# motherboard.net
KiCad netlist of a schematic drawn in EAGLE
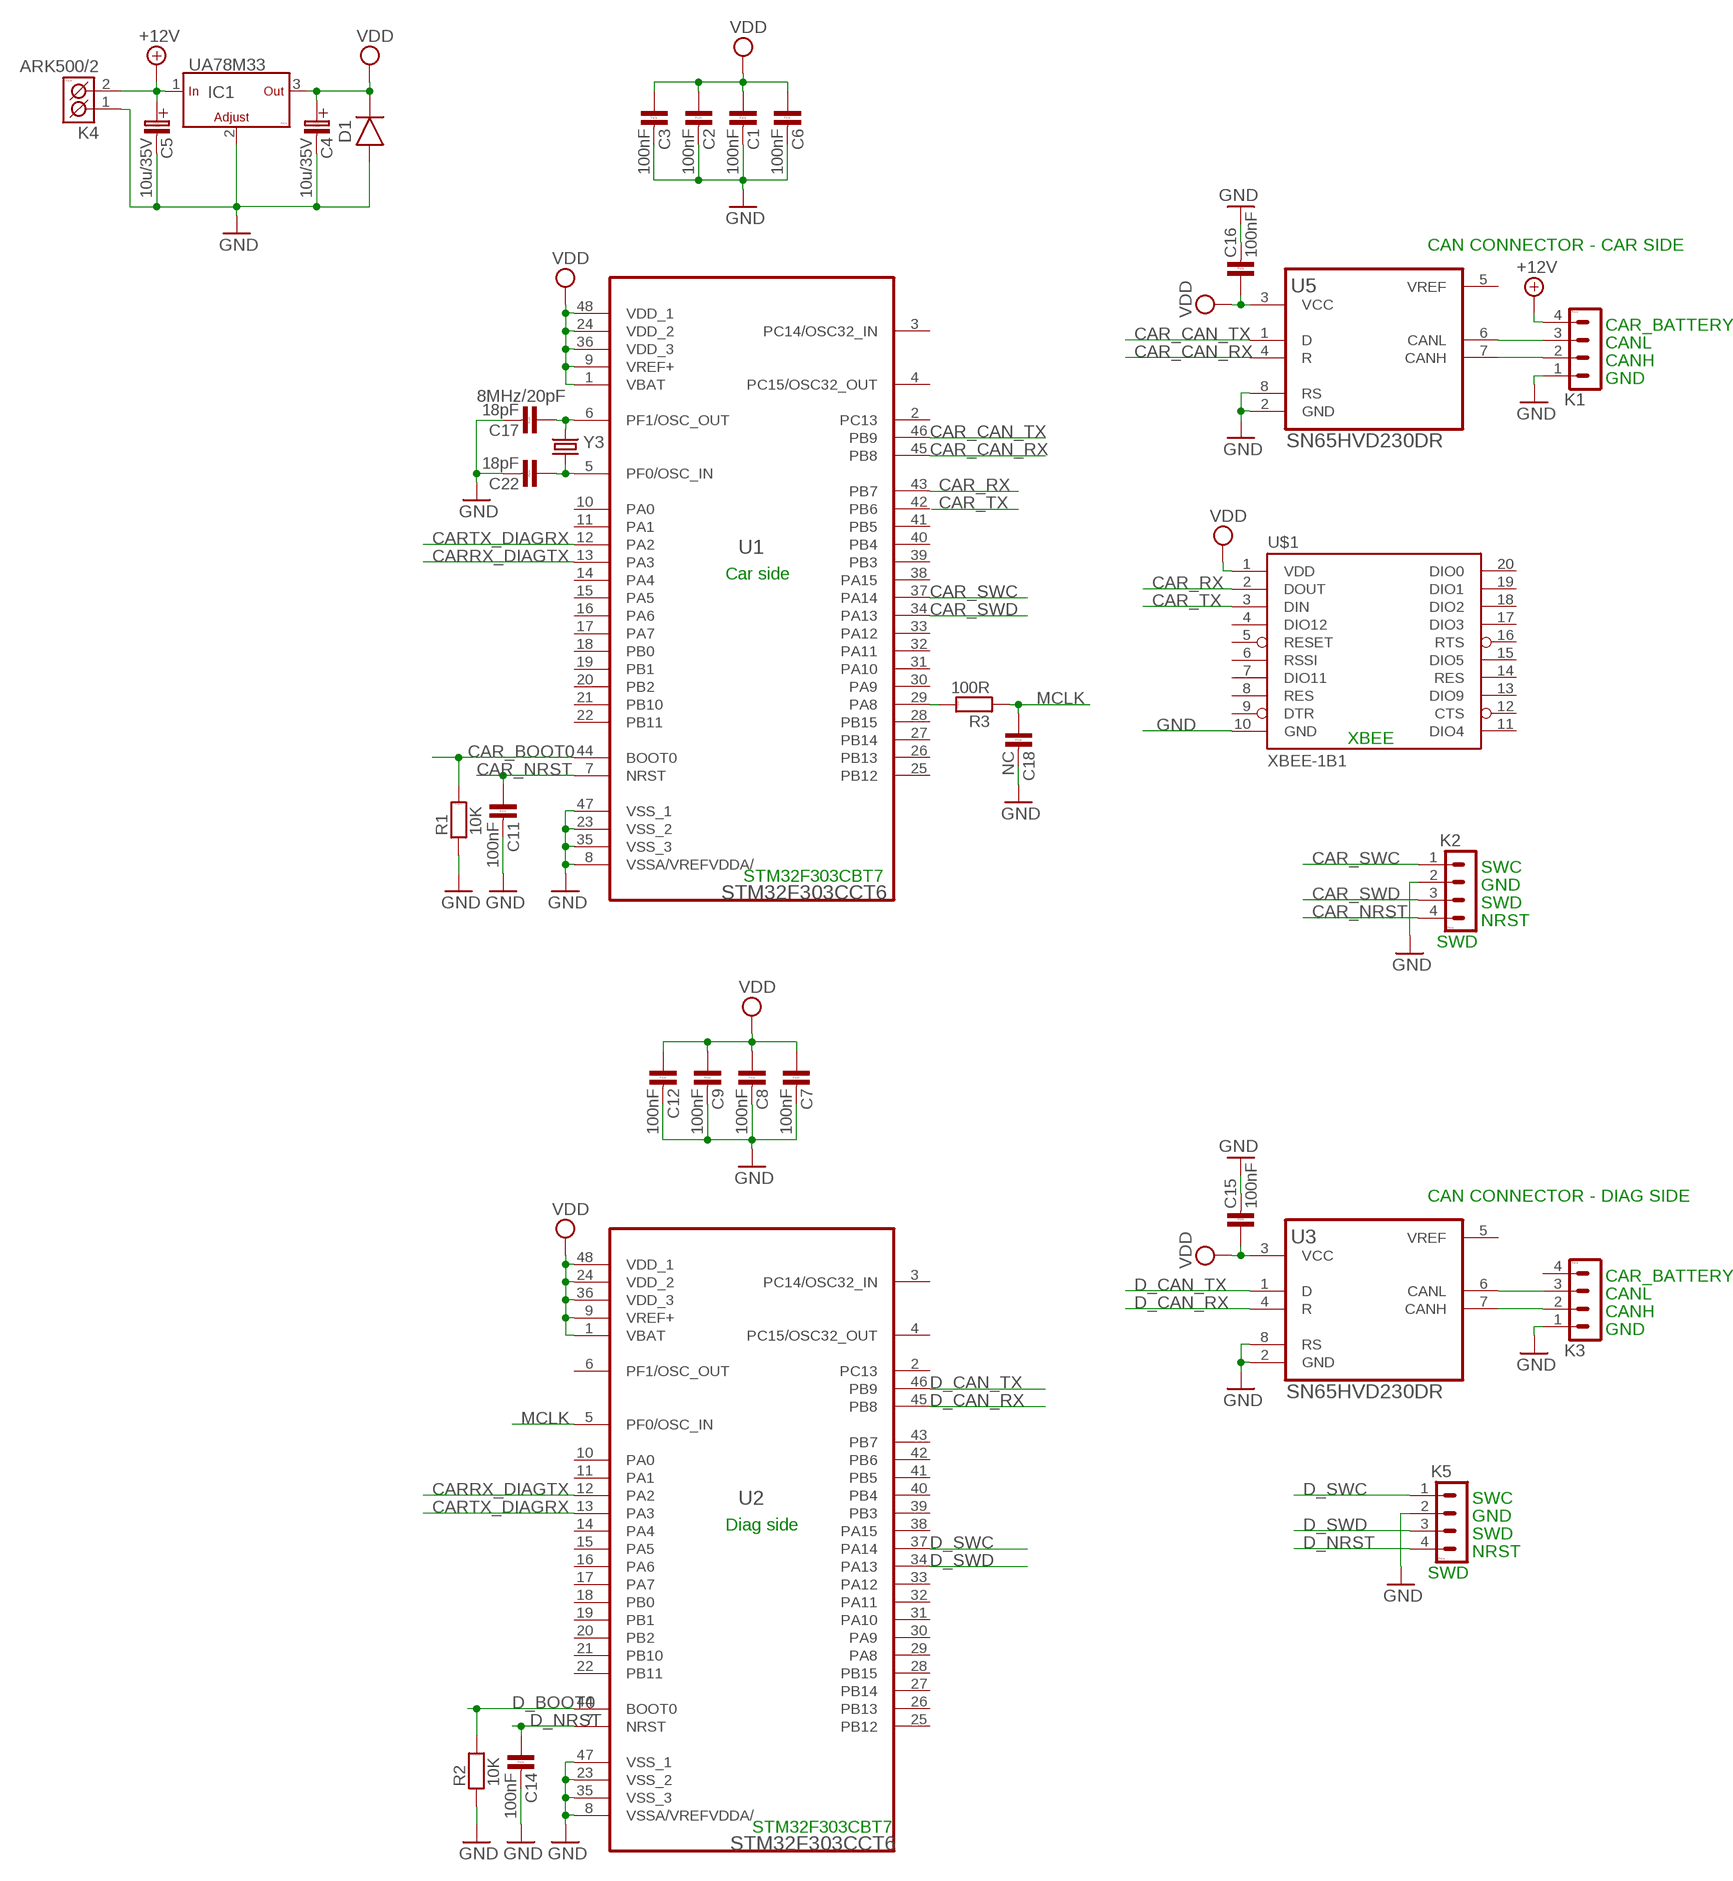
[diagram p0: schematic, sheet 1]

(export (version "E")
  (design (tool "Eeschema 10.0.6"))
  (components
    (comp (ref "C1")
      (value "100nF")
      (footprint "eagle-import:0805")
      (libsource (lib "eagle-import") (part "C-KERAMIK_SMD_0805"))
    )
    (comp (ref "C2")
      (value "100nF")
      (footprint "eagle-import:0805")
      (libsource (lib "eagle-import") (part "C-KERAMIK_SMD_0805"))
    )
    (comp (ref "C3")
      (value "100nF")
      (footprint "eagle-import:0805")
      (libsource (lib "eagle-import") (part "C-KERAMIK_SMD_0805"))
    )
    (comp (ref "C4")
      (value "10u/35V")
      (footprint "eagle-import:C-EL_2,5")
      (libsource (lib "eagle-import") (part "C-ELEKTROLYT_2,5"))
    )
    (comp (ref "C5")
      (value "10u/35V")
      (footprint "eagle-import:C-EL_2,5")
      (libsource (lib "eagle-import") (part "C-ELEKTROLYT_2,5"))
    )
    (comp (ref "C6")
      (value "100nF")
      (footprint "eagle-import:0805")
      (libsource (lib "eagle-import") (part "C-KERAMIK_SMD_0805"))
    )
    (comp (ref "C7")
      (value "100nF")
      (footprint "eagle-import:0805")
      (libsource (lib "eagle-import") (part "C-KERAMIK_SMD_0805"))
    )
    (comp (ref "C8")
      (value "100nF")
      (footprint "eagle-import:0805")
      (libsource (lib "eagle-import") (part "C-KERAMIK_SMD_0805"))
    )
    (comp (ref "C9")
      (value "100nF")
      (footprint "eagle-import:0805")
      (libsource (lib "eagle-import") (part "C-KERAMIK_SMD_0805"))
    )
    (comp (ref "C11")
      (value "100nF")
      (footprint "eagle-import:0805")
      (libsource (lib "eagle-import") (part "C-KERAMIK_SMD_0805"))
    )
    (comp (ref "C12")
      (value "100nF")
      (footprint "eagle-import:0805")
      (libsource (lib "eagle-import") (part "C-KERAMIK_SMD_0805"))
    )
    (comp (ref "C14")
      (value "100nF")
      (footprint "eagle-import:0805")
      (libsource (lib "eagle-import") (part "C-KERAMIK_SMD_0805"))
    )
    (comp (ref "C15")
      (value "100nF")
      (footprint "eagle-import:0805")
      (libsource (lib "eagle-import") (part "C-KERAMIK_SMD_0805"))
    )
    (comp (ref "C16")
      (value "100nF")
      (footprint "eagle-import:0805")
      (libsource (lib "eagle-import") (part "C-KERAMIK_SMD_0805"))
    )
    (comp (ref "C17")
      (value "18pF")
      (footprint "eagle-import:1206")
      (libsource (lib "eagle-import") (part "C-KERAMIK_SMD_1206"))
    )
    (comp (ref "C18")
      (value "NC")
      (footprint "eagle-import:0805")
      (libsource (lib "eagle-import") (part "C-KERAMIK_SMD_0805"))
    )
    (comp (ref "C22")
      (value "18pF")
      (footprint "eagle-import:1206")
      (libsource (lib "eagle-import") (part "C-KERAMIK_SMD_1206"))
    )
    (comp (ref "D1")
      (value "1N4007SMD")
      (footprint "eagle-import:MELF")
      (libsource (lib "eagle-import") (part "1N4007SMD"))
    )
    (comp (ref "IC1")
      (value "UA78M33")
      (footprint "eagle-import:TO285P991X230-3N")
      (fields (field (name "MPN") "UA78M33CKVURG3"))
      (libsource (lib "eagle-import") (part "UA78M33"))
    )
    (comp (ref "K1")
      (value "PSH02-04P")
      (footprint "eagle-import:PSH02-04P")
      (libsource (lib "eagle-import") (part "PSH02-04P"))
    )
    (comp (ref "K2")
      (value "PSH02-04P")
      (footprint "eagle-import:PSH02-04P")
      (libsource (lib "eagle-import") (part "PSH02-04P"))
    )
    (comp (ref "K3")
      (value "PSH02-04P")
      (footprint "eagle-import:PSH02-04P")
      (libsource (lib "eagle-import") (part "PSH02-04P"))
    )
    (comp (ref "K4")
      (value "ARK500/2")
      (footprint "eagle-import:ARK500_2")
      (libsource (lib "eagle-import") (part "ARK500/2"))
    )
    (comp (ref "K5")
      (value "PSH02-04P")
      (footprint "eagle-import:PSH02-04P")
      (libsource (lib "eagle-import") (part "PSH02-04P"))
    )
    (comp (ref "R1")
      (value "10K")
      (footprint "eagle-import:0805")
      (libsource (lib "eagle-import") (part "R_SMD_0805"))
    )
    (comp (ref "R2")
      (value "10K")
      (footprint "eagle-import:0805")
      (libsource (lib "eagle-import") (part "R_SMD_0805"))
    )
    (comp (ref "R3")
      (value "100R")
      (footprint "eagle-import:0805")
      (libsource (lib "eagle-import") (part "R_SMD_0805"))
    )
    (comp (ref "U$1")
      (value "XBEE-1B1")
      (footprint "eagle-import:XBEE-1")
      (libsource (lib "eagle-import") (part "XBEE-1B1"))
    )
    (comp (ref "U1")
      (value "STM32F303CCT6")
      (footprint "eagle-import:QFP50P900X900X160-48N")
      (libsource (lib "eagle-import") (part "STM32F303CCT6"))
    )
    (comp (ref "U2")
      (value "STM32F303CCT6")
      (footprint "eagle-import:QFP50P900X900X160-48N")
      (libsource (lib "eagle-import") (part "STM32F303CCT6"))
    )
    (comp (ref "U3")
      (value "SN65HVD230DR")
      (footprint "eagle-import:SOIC127P600X175-8N")
      (libsource (lib "eagle-import") (part "SN65HVD230DR"))
    )
    (comp (ref "U5")
      (value "SN65HVD230DR")
      (footprint "eagle-import:SOIC127P600X175-8N")
      (libsource (lib "eagle-import") (part "SN65HVD230DR"))
    )
    (comp (ref "Y3")
      (value "8MHz/20pF")
      (footprint "eagle-import:HC49UP")
      (libsource (lib "eagle-import") (part "CRYSTALSMD"))
    )
  )
  (nets
    (net (code "1") (name "+12V") (class "Default")
      (node (ref "C5") (pin "C+") (pinfunction "C_EL+_C+") (pintype "passive"))
      (node (ref "IC1") (pin "1") (pinfunction "IN_1") (pintype "input"))
      (node (ref "K1") (pin "4") (pinfunction "4_4") (pintype "passive"))
      (node (ref "K4") (pin "2") (pinfunction "K2_2") (pintype "passive"))
    )
    (net (code "2") (name "/CARRX_DIAGTX") (class "Default")
      (node (ref "U1") (pin "13") (pinfunction "PA3_13") (pintype "bidirectional"))
      (node (ref "U2") (pin "12") (pinfunction "PA2_12") (pintype "bidirectional"))
    )
    (net (code "3") (name "/CARTX_DIAGRX") (class "Default")
      (node (ref "U1") (pin "12") (pinfunction "PA2_12") (pintype "bidirectional"))
      (node (ref "U2") (pin "13") (pinfunction "PA3_13") (pintype "bidirectional"))
    )
    (net (code "4") (name "/CAR_BOOT0") (class "Default")
      (node (ref "R1") (pin "2") (pinfunction "2_2") (pintype "passive"))
      (node (ref "U1") (pin "44") (pinfunction "BOOT0_44") (pintype "passive"))
    )
    (net (code "5") (name "/CAR_CAN_RX") (class "Default")
      (node (ref "U1") (pin "45") (pinfunction "PB8_45") (pintype "bidirectional"))
      (node (ref "U5") (pin "4") (pinfunction "R_4") (pintype "output"))
    )
    (net (code "6") (name "/CAR_CAN_TX") (class "Default")
      (node (ref "U1") (pin "46") (pinfunction "PB9_46") (pintype "bidirectional"))
      (node (ref "U5") (pin "1") (pinfunction "D_1") (pintype "input"))
    )
    (net (code "7") (name "/CAR_NRST") (class "Default")
      (node (ref "C11") (pin "1") (pinfunction "1_1") (pintype "passive"))
      (node (ref "K2") (pin "4") (pinfunction "4_4") (pintype "passive"))
      (node (ref "U1") (pin "7") (pinfunction "NRST_7") (pintype "passive"))
    )
    (net (code "8") (name "/CAR_RX") (class "Default")
      (node (ref "U$1") (pin "2") (pinfunction "DOUT_2") (pintype "output"))
      (node (ref "U1") (pin "43") (pinfunction "PB7_43") (pintype "bidirectional"))
    )
    (net (code "9") (name "/CAR_SWC") (class "Default")
      (node (ref "K2") (pin "1") (pinfunction "1_1") (pintype "passive"))
      (node (ref "U1") (pin "37") (pinfunction "PA14_37") (pintype "bidirectional"))
    )
    (net (code "10") (name "/CAR_SWD") (class "Default")
      (node (ref "K2") (pin "3") (pinfunction "3_3") (pintype "passive"))
      (node (ref "U1") (pin "34") (pinfunction "PA13_34") (pintype "bidirectional"))
    )
    (net (code "11") (name "/CAR_TX") (class "Default")
      (node (ref "U$1") (pin "3") (pinfunction "DIN_3") (pintype "input"))
    )
    (net (code "12") (name "/D_BOOT0") (class "Default")
      (node (ref "R2") (pin "2") (pinfunction "2_2") (pintype "passive"))
      (node (ref "U2") (pin "44") (pinfunction "BOOT0_44") (pintype "passive"))
    )
    (net (code "13") (name "/D_CAN_RX") (class "Default")
      (node (ref "U2") (pin "45") (pinfunction "PB8_45") (pintype "bidirectional"))
      (node (ref "U3") (pin "4") (pinfunction "R_4") (pintype "output"))
    )
    (net (code "14") (name "/D_CAN_TX") (class "Default")
      (node (ref "U2") (pin "46") (pinfunction "PB9_46") (pintype "bidirectional"))
      (node (ref "U3") (pin "1") (pinfunction "D_1") (pintype "input"))
    )
    (net (code "15") (name "/D_NRST") (class "Default")
      (node (ref "C14") (pin "1") (pinfunction "1_1") (pintype "passive"))
      (node (ref "K5") (pin "4") (pinfunction "4_4") (pintype "passive"))
      (node (ref "U2") (pin "7") (pinfunction "NRST_7") (pintype "passive"))
    )
    (net (code "16") (name "/D_SWC") (class "Default")
      (node (ref "K5") (pin "1") (pinfunction "1_1") (pintype "passive"))
      (node (ref "U2") (pin "37") (pinfunction "PA14_37") (pintype "bidirectional"))
    )
    (net (code "17") (name "/D_SWD") (class "Default")
      (node (ref "K5") (pin "3") (pinfunction "3_3") (pintype "passive"))
      (node (ref "U2") (pin "34") (pinfunction "PA13_34") (pintype "bidirectional"))
    )
    (net (code "18") (name "/MCLK") (class "Default")
      (node (ref "C18") (pin "1") (pinfunction "1_1") (pintype "passive"))
      (node (ref "R3") (pin "1") (pinfunction "1_1") (pintype "passive"))
      (node (ref "U2") (pin "5") (pinfunction "PF0/OSC_IN_5") (pintype "bidirectional"))
    )
    (net (code "19") (name "GND") (class "Default")
      (node (ref "C1") (pin "2") (pinfunction "2_2") (pintype "passive"))
      (node (ref "C11") (pin "2") (pinfunction "2_2") (pintype "passive"))
      (node (ref "C12") (pin "2") (pinfunction "2_2") (pintype "passive"))
      (node (ref "C14") (pin "2") (pinfunction "2_2") (pintype "passive"))
      (node (ref "C15") (pin "2") (pinfunction "2_2") (pintype "passive"))
      (node (ref "C16") (pin "2") (pinfunction "2_2") (pintype "passive"))
      (node (ref "C17") (pin "2") (pinfunction "2_2") (pintype "passive"))
      (node (ref "C18") (pin "2") (pinfunction "2_2") (pintype "passive"))
      (node (ref "C2") (pin "2") (pinfunction "2_2") (pintype "passive"))
      (node (ref "C22") (pin "2") (pinfunction "2_2") (pintype "passive"))
      (node (ref "C3") (pin "2") (pinfunction "2_2") (pintype "passive"))
      (node (ref "C4") (pin "C-") (pinfunction "C_EL-_C-") (pintype "passive"))
      (node (ref "C5") (pin "C-") (pinfunction "C_EL-_C-") (pintype "passive"))
      (node (ref "C6") (pin "2") (pinfunction "2_2") (pintype "passive"))
      (node (ref "C7") (pin "2") (pinfunction "2_2") (pintype "passive"))
      (node (ref "C8") (pin "2") (pinfunction "2_2") (pintype "passive"))
      (node (ref "C9") (pin "2") (pinfunction "2_2") (pintype "passive"))
      (node (ref "D1") (pin "A") (pinfunction "A_A") (pintype "passive"))
      (node (ref "IC1") (pin "2") (pinfunction "ADJ_2") (pintype "input"))
      (node (ref "K1") (pin "1") (pinfunction "1_1") (pintype "passive"))
      (node (ref "K2") (pin "2") (pinfunction "2_2") (pintype "passive"))
      (node (ref "K3") (pin "1") (pinfunction "1_1") (pintype "passive"))
      (node (ref "K4") (pin "1") (pinfunction "K1_1") (pintype "passive"))
      (node (ref "K5") (pin "2") (pinfunction "2_2") (pintype "passive"))
      (node (ref "R1") (pin "1") (pinfunction "1_1") (pintype "passive"))
      (node (ref "R2") (pin "1") (pinfunction "1_1") (pintype "passive"))
      (node (ref "U$1") (pin "10") (pinfunction "GND_10") (pintype "power_in"))
      (node (ref "U1") (pin "23") (pinfunction "VSS_2_23") (pintype "power_in"))
      (node (ref "U1") (pin "35") (pinfunction "VSS_3_35") (pintype "power_in"))
      (node (ref "U1") (pin "47") (pinfunction "VSS_1_47") (pintype "power_in"))
      (node (ref "U1") (pin "8") (pinfunction "VSSA/VREFVDDA/_8") (pintype "power_in"))
      (node (ref "U2") (pin "23") (pinfunction "VSS_2_23") (pintype "power_in"))
      (node (ref "U2") (pin "35") (pinfunction "VSS_3_35") (pintype "power_in"))
      (node (ref "U2") (pin "47") (pinfunction "VSS_1_47") (pintype "power_in"))
      (node (ref "U2") (pin "8") (pinfunction "VSSA/VREFVDDA/_8") (pintype "power_in"))
      (node (ref "U3") (pin "2") (pinfunction "GND_2") (pintype "passive"))
      (node (ref "U3") (pin "8") (pinfunction "RS_8") (pintype "input"))
      (node (ref "U5") (pin "2") (pinfunction "GND_2") (pintype "passive"))
      (node (ref "U5") (pin "8") (pinfunction "RS_8") (pintype "input"))
    )
    (net (code "20") (name "Net-(U1-PA8)") (class "Default")
      (node (ref "R3") (pin "2") (pinfunction "2_2") (pintype "passive"))
      (node (ref "U1") (pin "29") (pinfunction "PA8_29") (pintype "bidirectional"))
    )
    (net (code "21") (name "Net-(U1-PF0{slash}OSC_IN)") (class "Default")
      (node (ref "C22") (pin "1") (pinfunction "1_1") (pintype "passive"))
      (node (ref "U1") (pin "5") (pinfunction "PF0/OSC_IN_5") (pintype "bidirectional"))
      (node (ref "Y3") (pin "1") (pinfunction "1_1") (pintype "passive"))
    )
    (net (code "22") (name "Net-(U1-PF1{slash}OSC_OUT)") (class "Default")
      (node (ref "C17") (pin "1") (pinfunction "1_1") (pintype "passive"))
      (node (ref "U1") (pin "6") (pinfunction "PF1/OSC_OUT_6") (pintype "bidirectional"))
      (node (ref "Y3") (pin "2") (pinfunction "2_2") (pintype "passive"))
    )
    (net (code "23") (name "Net-(U3-CANH)") (class "Default")
      (node (ref "K3") (pin "2") (pinfunction "2_2") (pintype "passive"))
      (node (ref "U3") (pin "7") (pinfunction "CANH_7") (pintype "output"))
    )
    (net (code "24") (name "Net-(U3-CANL)") (class "Default")
      (node (ref "K3") (pin "3") (pinfunction "3_3") (pintype "passive"))
      (node (ref "U3") (pin "6") (pinfunction "CANL_6") (pintype "output"))
    )
    (net (code "25") (name "Net-(U5-CANH)") (class "Default")
      (node (ref "K1") (pin "2") (pinfunction "2_2") (pintype "passive"))
      (node (ref "U5") (pin "7") (pinfunction "CANH_7") (pintype "output"))
    )
    (net (code "26") (name "Net-(U5-CANL)") (class "Default")
      (node (ref "K1") (pin "3") (pinfunction "3_3") (pintype "passive"))
      (node (ref "U5") (pin "6") (pinfunction "CANL_6") (pintype "output"))
    )
    (net (code "27") (name "VDD") (class "Default")
      (node (ref "C1") (pin "1") (pinfunction "1_1") (pintype "passive"))
      (node (ref "C12") (pin "1") (pinfunction "1_1") (pintype "passive"))
      (node (ref "C15") (pin "1") (pinfunction "1_1") (pintype "passive"))
      (node (ref "C16") (pin "1") (pinfunction "1_1") (pintype "passive"))
      (node (ref "C2") (pin "1") (pinfunction "1_1") (pintype "passive"))
      (node (ref "C3") (pin "1") (pinfunction "1_1") (pintype "passive"))
      (node (ref "C4") (pin "C+") (pinfunction "C_EL+_C+") (pintype "passive"))
      (node (ref "C6") (pin "1") (pinfunction "1_1") (pintype "passive"))
      (node (ref "C7") (pin "1") (pinfunction "1_1") (pintype "passive"))
      (node (ref "C8") (pin "1") (pinfunction "1_1") (pintype "passive"))
      (node (ref "C9") (pin "1") (pinfunction "1_1") (pintype "passive"))
      (node (ref "D1") (pin "K") (pinfunction "K_K") (pintype "passive"))
      (node (ref "IC1") (pin "3") (pinfunction "OUT_3") (pintype "output"))
      (node (ref "U$1") (pin "1") (pinfunction "VDD_1") (pintype "power_in"))
      (node (ref "U1") (pin "1") (pinfunction "VBAT_1") (pintype "passive"))
      (node (ref "U1") (pin "24") (pinfunction "VDD_2_24") (pintype "power_in"))
      (node (ref "U1") (pin "36") (pinfunction "VDD_3_36") (pintype "power_in"))
      (node (ref "U1") (pin "48") (pinfunction "VDD_1_48") (pintype "power_in"))
      (node (ref "U1") (pin "9") (pinfunction "VREF+_9") (pintype "passive"))
      (node (ref "U2") (pin "1") (pinfunction "VBAT_1") (pintype "passive"))
      (node (ref "U2") (pin "24") (pinfunction "VDD_2_24") (pintype "power_in"))
      (node (ref "U2") (pin "36") (pinfunction "VDD_3_36") (pintype "power_in"))
      (node (ref "U2") (pin "48") (pinfunction "VDD_1_48") (pintype "power_in"))
      (node (ref "U2") (pin "9") (pinfunction "VREF+_9") (pintype "passive"))
      (node (ref "U3") (pin "3") (pinfunction "VCC_3") (pintype "power_in"))
      (node (ref "U5") (pin "3") (pinfunction "VCC_3") (pintype "power_in"))
    )
    (net (code "28") (name "unconnected-(K3-Pad4)") (class "Default")
      (node (ref "K3") (pin "4") (pinfunction "4_4") (pintype "passive"))
    )
    (net (code "29") (name "unconnected-(U$1-CTS-Pad12)") (class "Default")
      (node (ref "U$1") (pin "12") (pinfunction "CTS_12") (pintype "output"))
    )
    (net (code "30") (name "unconnected-(U$1-DIO0-Pad20)") (class "Default")
      (node (ref "U$1") (pin "20") (pinfunction "DIO0_20") (pintype "bidirectional"))
    )
    (net (code "31") (name "unconnected-(U$1-DIO1-Pad19)") (class "Default")
      (node (ref "U$1") (pin "19") (pinfunction "DIO1_19") (pintype "bidirectional"))
    )
    (net (code "32") (name "unconnected-(U$1-DIO2-Pad18)") (class "Default")
      (node (ref "U$1") (pin "18") (pinfunction "DIO2_18") (pintype "bidirectional"))
    )
    (net (code "33") (name "unconnected-(U$1-DIO3-Pad17)") (class "Default")
      (node (ref "U$1") (pin "17") (pinfunction "DIO3_17") (pintype "bidirectional"))
    )
    (net (code "34") (name "unconnected-(U$1-DIO4-Pad11)") (class "Default")
      (node (ref "U$1") (pin "11") (pinfunction "DIO4_11") (pintype "bidirectional"))
    )
    (net (code "35") (name "unconnected-(U$1-DIO5-Pad15)") (class "Default")
      (node (ref "U$1") (pin "15") (pinfunction "DIO5_15") (pintype "bidirectional"))
    )
    (net (code "36") (name "unconnected-(U$1-DIO9-Pad13)") (class "Default")
      (node (ref "U$1") (pin "13") (pinfunction "DIO9_13") (pintype "bidirectional"))
    )
    (net (code "37") (name "unconnected-(U$1-DIO11-Pad7)") (class "Default")
      (node (ref "U$1") (pin "7") (pinfunction "DIO11_7") (pintype "bidirectional"))
    )
    (net (code "38") (name "unconnected-(U$1-DIO12-Pad4)") (class "Default")
      (node (ref "U$1") (pin "4") (pinfunction "DIO12_4") (pintype "bidirectional"))
    )
    (net (code "39") (name "unconnected-(U$1-DTR-Pad9)") (class "Default")
      (node (ref "U$1") (pin "9") (pinfunction "DTR_9") (pintype "bidirectional"))
    )
    (net (code "40") (name "unconnected-(U$1-RES-Pad8)") (class "Default")
      (node (ref "U$1") (pin "8") (pinfunction "RES_8") (pintype "bidirectional"))
    )
    (net (code "41") (name "unconnected-(U$1-RES-Pad14)") (class "Default")
      (node (ref "U$1") (pin "14") (pinfunction "RES_14") (pintype "bidirectional"))
    )
    (net (code "42") (name "unconnected-(U$1-RESET-Pad5)") (class "Default")
      (node (ref "U$1") (pin "5") (pinfunction "RESET_5") (pintype "input"))
    )
    (net (code "43") (name "unconnected-(U$1-RSSI-Pad6)") (class "Default")
      (node (ref "U$1") (pin "6") (pinfunction "RSSI_6") (pintype "bidirectional"))
    )
    (net (code "44") (name "unconnected-(U$1-RTS-Pad16)") (class "Default")
      (node (ref "U$1") (pin "16") (pinfunction "RTS_16") (pintype "input"))
    )
    (net (code "45") (name "unconnected-(U1-PA0-Pad10)") (class "Default")
      (node (ref "U1") (pin "10") (pinfunction "PA0_10") (pintype "bidirectional"))
    )
    (net (code "46") (name "unconnected-(U1-PA1-Pad11)") (class "Default")
      (node (ref "U1") (pin "11") (pinfunction "PA1_11") (pintype "bidirectional"))
    )
    (net (code "47") (name "unconnected-(U1-PA4-Pad14)") (class "Default")
      (node (ref "U1") (pin "14") (pinfunction "PA4_14") (pintype "bidirectional"))
    )
    (net (code "48") (name "unconnected-(U1-PA5-Pad15)") (class "Default")
      (node (ref "U1") (pin "15") (pinfunction "PA5_15") (pintype "bidirectional"))
    )
    (net (code "49") (name "unconnected-(U1-PA6-Pad16)") (class "Default")
      (node (ref "U1") (pin "16") (pinfunction "PA6_16") (pintype "bidirectional"))
    )
    (net (code "50") (name "unconnected-(U1-PA7-Pad17)") (class "Default")
      (node (ref "U1") (pin "17") (pinfunction "PA7_17") (pintype "bidirectional"))
    )
    (net (code "51") (name "unconnected-(U1-PA9-Pad30)") (class "Default")
      (node (ref "U1") (pin "30") (pinfunction "PA9_30") (pintype "bidirectional"))
    )
    (net (code "52") (name "unconnected-(U1-PA10-Pad31)") (class "Default")
      (node (ref "U1") (pin "31") (pinfunction "PA10_31") (pintype "bidirectional"))
    )
    (net (code "53") (name "unconnected-(U1-PA11-Pad32)") (class "Default")
      (node (ref "U1") (pin "32") (pinfunction "PA11_32") (pintype "bidirectional"))
    )
    (net (code "54") (name "unconnected-(U1-PA12-Pad33)") (class "Default")
      (node (ref "U1") (pin "33") (pinfunction "PA12_33") (pintype "bidirectional"))
    )
    (net (code "55") (name "unconnected-(U1-PA15-Pad38)") (class "Default")
      (node (ref "U1") (pin "38") (pinfunction "PA15_38") (pintype "bidirectional"))
    )
    (net (code "56") (name "unconnected-(U1-PB0-Pad18)") (class "Default")
      (node (ref "U1") (pin "18") (pinfunction "PB0_18") (pintype "bidirectional"))
    )
    (net (code "57") (name "unconnected-(U1-PB1-Pad19)") (class "Default")
      (node (ref "U1") (pin "19") (pinfunction "PB1_19") (pintype "bidirectional"))
    )
    (net (code "58") (name "unconnected-(U1-PB2-Pad20)") (class "Default")
      (node (ref "U1") (pin "20") (pinfunction "PB2_20") (pintype "bidirectional"))
    )
    (net (code "59") (name "unconnected-(U1-PB3-Pad39)") (class "Default")
      (node (ref "U1") (pin "39") (pinfunction "PB3_39") (pintype "bidirectional"))
    )
    (net (code "60") (name "unconnected-(U1-PB4-Pad40)") (class "Default")
      (node (ref "U1") (pin "40") (pinfunction "PB4_40") (pintype "bidirectional"))
    )
    (net (code "61") (name "unconnected-(U1-PB5-Pad41)") (class "Default")
      (node (ref "U1") (pin "41") (pinfunction "PB5_41") (pintype "bidirectional"))
    )
    (net (code "62") (name "unconnected-(U1-PB6-Pad42)") (class "Default")
      (node (ref "U1") (pin "42") (pinfunction "PB6_42") (pintype "bidirectional"))
    )
    (net (code "63") (name "unconnected-(U1-PB10-Pad21)") (class "Default")
      (node (ref "U1") (pin "21") (pinfunction "PB10_21") (pintype "bidirectional"))
    )
    (net (code "64") (name "unconnected-(U1-PB11-Pad22)") (class "Default")
      (node (ref "U1") (pin "22") (pinfunction "PB11_22") (pintype "bidirectional"))
    )
    (net (code "65") (name "unconnected-(U1-PB12-Pad25)") (class "Default")
      (node (ref "U1") (pin "25") (pinfunction "PB12_25") (pintype "bidirectional"))
    )
    (net (code "66") (name "unconnected-(U1-PB13-Pad26)") (class "Default")
      (node (ref "U1") (pin "26") (pinfunction "PB13_26") (pintype "bidirectional"))
    )
    (net (code "67") (name "unconnected-(U1-PB14-Pad27)") (class "Default")
      (node (ref "U1") (pin "27") (pinfunction "PB14_27") (pintype "bidirectional"))
    )
    (net (code "68") (name "unconnected-(U1-PB15-Pad28)") (class "Default")
      (node (ref "U1") (pin "28") (pinfunction "PB15_28") (pintype "bidirectional"))
    )
    (net (code "69") (name "unconnected-(U1-PC13-Pad2)") (class "Default")
      (node (ref "U1") (pin "2") (pinfunction "PC13_2") (pintype "bidirectional"))
    )
    (net (code "70") (name "unconnected-(U1-PC14{slash}OSC32_IN-Pad3)") (class "Default")
      (node (ref "U1") (pin "3") (pinfunction "PC14/OSC32_IN_3") (pintype "bidirectional"))
    )
    (net (code "71") (name "unconnected-(U1-PC15{slash}OSC32_OUT-Pad4)") (class "Default")
      (node (ref "U1") (pin "4") (pinfunction "PC15/OSC32_OUT_4") (pintype "bidirectional"))
    )
    (net (code "72") (name "unconnected-(U2-PA0-Pad10)") (class "Default")
      (node (ref "U2") (pin "10") (pinfunction "PA0_10") (pintype "bidirectional"))
    )
    (net (code "73") (name "unconnected-(U2-PA1-Pad11)") (class "Default")
      (node (ref "U2") (pin "11") (pinfunction "PA1_11") (pintype "bidirectional"))
    )
    (net (code "74") (name "unconnected-(U2-PA4-Pad14)") (class "Default")
      (node (ref "U2") (pin "14") (pinfunction "PA4_14") (pintype "bidirectional"))
    )
    (net (code "75") (name "unconnected-(U2-PA5-Pad15)") (class "Default")
      (node (ref "U2") (pin "15") (pinfunction "PA5_15") (pintype "bidirectional"))
    )
    (net (code "76") (name "unconnected-(U2-PA6-Pad16)") (class "Default")
      (node (ref "U2") (pin "16") (pinfunction "PA6_16") (pintype "bidirectional"))
    )
    (net (code "77") (name "unconnected-(U2-PA7-Pad17)") (class "Default")
      (node (ref "U2") (pin "17") (pinfunction "PA7_17") (pintype "bidirectional"))
    )
    (net (code "78") (name "unconnected-(U2-PA8-Pad29)") (class "Default")
      (node (ref "U2") (pin "29") (pinfunction "PA8_29") (pintype "bidirectional"))
    )
    (net (code "79") (name "unconnected-(U2-PA9-Pad30)") (class "Default")
      (node (ref "U2") (pin "30") (pinfunction "PA9_30") (pintype "bidirectional"))
    )
    (net (code "80") (name "unconnected-(U2-PA10-Pad31)") (class "Default")
      (node (ref "U2") (pin "31") (pinfunction "PA10_31") (pintype "bidirectional"))
    )
    (net (code "81") (name "unconnected-(U2-PA11-Pad32)") (class "Default")
      (node (ref "U2") (pin "32") (pinfunction "PA11_32") (pintype "bidirectional"))
    )
    (net (code "82") (name "unconnected-(U2-PA12-Pad33)") (class "Default")
      (node (ref "U2") (pin "33") (pinfunction "PA12_33") (pintype "bidirectional"))
    )
    (net (code "83") (name "unconnected-(U2-PA15-Pad38)") (class "Default")
      (node (ref "U2") (pin "38") (pinfunction "PA15_38") (pintype "bidirectional"))
    )
    (net (code "84") (name "unconnected-(U2-PB0-Pad18)") (class "Default")
      (node (ref "U2") (pin "18") (pinfunction "PB0_18") (pintype "bidirectional"))
    )
    (net (code "85") (name "unconnected-(U2-PB1-Pad19)") (class "Default")
      (node (ref "U2") (pin "19") (pinfunction "PB1_19") (pintype "bidirectional"))
    )
    (net (code "86") (name "unconnected-(U2-PB2-Pad20)") (class "Default")
      (node (ref "U2") (pin "20") (pinfunction "PB2_20") (pintype "bidirectional"))
    )
    (net (code "87") (name "unconnected-(U2-PB3-Pad39)") (class "Default")
      (node (ref "U2") (pin "39") (pinfunction "PB3_39") (pintype "bidirectional"))
    )
    (net (code "88") (name "unconnected-(U2-PB4-Pad40)") (class "Default")
      (node (ref "U2") (pin "40") (pinfunction "PB4_40") (pintype "bidirectional"))
    )
    (net (code "89") (name "unconnected-(U2-PB5-Pad41)") (class "Default")
      (node (ref "U2") (pin "41") (pinfunction "PB5_41") (pintype "bidirectional"))
    )
    (net (code "90") (name "unconnected-(U2-PB6-Pad42)") (class "Default")
      (node (ref "U2") (pin "42") (pinfunction "PB6_42") (pintype "bidirectional"))
    )
    (net (code "91") (name "unconnected-(U2-PB7-Pad43)") (class "Default")
      (node (ref "U2") (pin "43") (pinfunction "PB7_43") (pintype "bidirectional"))
    )
    (net (code "92") (name "unconnected-(U2-PB10-Pad21)") (class "Default")
      (node (ref "U2") (pin "21") (pinfunction "PB10_21") (pintype "bidirectional"))
    )
    (net (code "93") (name "unconnected-(U2-PB11-Pad22)") (class "Default")
      (node (ref "U2") (pin "22") (pinfunction "PB11_22") (pintype "bidirectional"))
    )
    (net (code "94") (name "unconnected-(U2-PB12-Pad25)") (class "Default")
      (node (ref "U2") (pin "25") (pinfunction "PB12_25") (pintype "bidirectional"))
    )
    (net (code "95") (name "unconnected-(U2-PB13-Pad26)") (class "Default")
      (node (ref "U2") (pin "26") (pinfunction "PB13_26") (pintype "bidirectional"))
    )
    (net (code "96") (name "unconnected-(U2-PB14-Pad27)") (class "Default")
      (node (ref "U2") (pin "27") (pinfunction "PB14_27") (pintype "bidirectional"))
    )
    (net (code "97") (name "unconnected-(U2-PB15-Pad28)") (class "Default")
      (node (ref "U2") (pin "28") (pinfunction "PB15_28") (pintype "bidirectional"))
    )
    (net (code "98") (name "unconnected-(U2-PC13-Pad2)") (class "Default")
      (node (ref "U2") (pin "2") (pinfunction "PC13_2") (pintype "bidirectional"))
    )
    (net (code "99") (name "unconnected-(U2-PC14{slash}OSC32_IN-Pad3)") (class "Default")
      (node (ref "U2") (pin "3") (pinfunction "PC14/OSC32_IN_3") (pintype "bidirectional"))
    )
    (net (code "100") (name "unconnected-(U2-PC15{slash}OSC32_OUT-Pad4)") (class "Default")
      (node (ref "U2") (pin "4") (pinfunction "PC15/OSC32_OUT_4") (pintype "bidirectional"))
    )
    (net (code "101") (name "unconnected-(U2-PF1{slash}OSC_OUT-Pad6)") (class "Default")
      (node (ref "U2") (pin "6") (pinfunction "PF1/OSC_OUT_6") (pintype "bidirectional"))
    )
    (net (code "102") (name "unconnected-(U3-VREF-Pad5)") (class "Default")
      (node (ref "U3") (pin "5") (pinfunction "VREF_5") (pintype "output"))
    )
    (net (code "103") (name "unconnected-(U5-VREF-Pad5)") (class "Default")
      (node (ref "U5") (pin "5") (pinfunction "VREF_5") (pintype "output"))
    )
  )
)
